# mcb-enhancer-v5.net
KiCad netlist of a schematic drawn in EAGLE
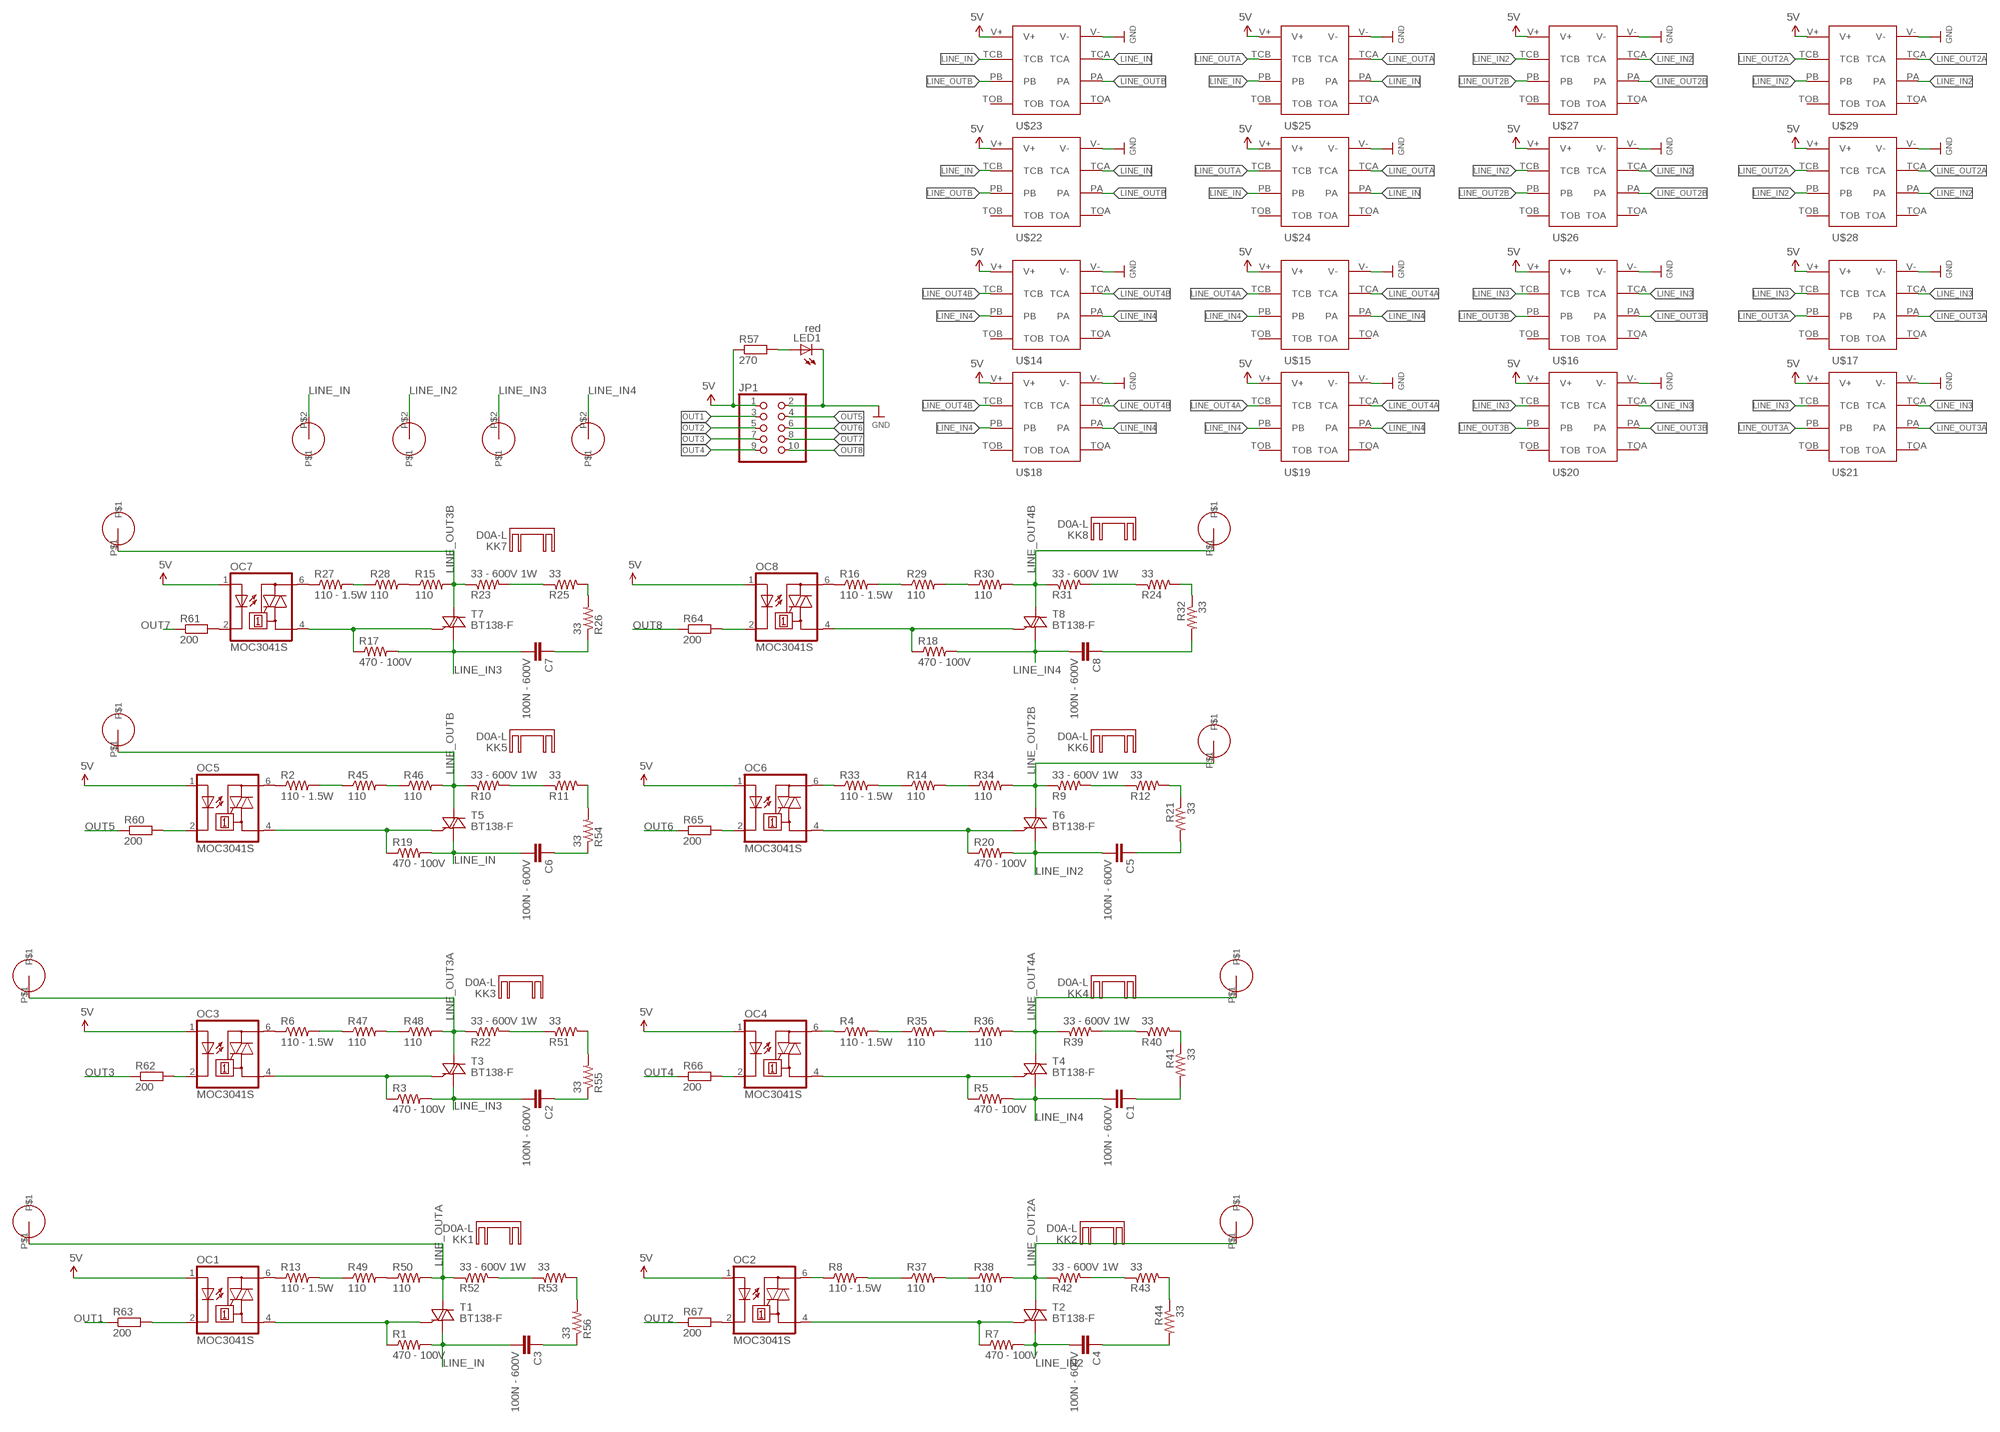
[diagram p0: schematic, sheet 1]

(export (version "E")
  (design (tool "Eeschema 10.0.6"))
  (components
    (comp (ref "C1")
      (value "100N - 600V")
      (footprint "eagle-import:C1210")
      (libsource (lib "eagle-import") (part "C-EUC1210"))
    )
    (comp (ref "C2")
      (value "100N - 600V")
      (footprint "eagle-import:C1210")
      (libsource (lib "eagle-import") (part "C-EUC1210"))
    )
    (comp (ref "C3")
      (value "100N - 600V")
      (footprint "eagle-import:C1210")
      (libsource (lib "eagle-import") (part "C-EUC1210"))
    )
    (comp (ref "C4")
      (value "100N - 600V")
      (footprint "eagle-import:C1210")
      (libsource (lib "eagle-import") (part "C-EUC1210"))
    )
    (comp (ref "C5")
      (value "100N - 600V")
      (footprint "eagle-import:C1210")
      (libsource (lib "eagle-import") (part "C-EUC1210"))
    )
    (comp (ref "C6")
      (value "100N - 600V")
      (footprint "eagle-import:C1210")
      (libsource (lib "eagle-import") (part "C-EUC1210"))
    )
    (comp (ref "C7")
      (value "100N - 600V")
      (footprint "eagle-import:C1210")
      (libsource (lib "eagle-import") (part "C-EUC1210"))
    )
    (comp (ref "C8")
      (value "100N - 600V")
      (footprint "eagle-import:C1210")
      (libsource (lib "eagle-import") (part "C-EUC1210"))
    )
    (comp (ref "JP1")
      (value "PINHD-2X5")
      (footprint "eagle-import:2X05")
      (libsource (lib "eagle-import") (part "PINHD-2X5"))
    )
    (comp (ref "KK1")
      (value "D0A-L")
      (footprint "eagle-import:D02A-L")
      (libsource (lib "eagle-import") (part "D0A-L"))
    )
    (comp (ref "KK2")
      (value "D0A-L")
      (footprint "eagle-import:D02A-L")
      (libsource (lib "eagle-import") (part "D0A-L"))
    )
    (comp (ref "KK3")
      (value "D0A-L")
      (footprint "eagle-import:D02A-L")
      (libsource (lib "eagle-import") (part "D0A-L"))
    )
    (comp (ref "KK4")
      (value "D0A-L")
      (footprint "eagle-import:D02A-L")
      (libsource (lib "eagle-import") (part "D0A-L"))
    )
    (comp (ref "KK5")
      (value "D0A-L")
      (footprint "eagle-import:D02A-L")
      (libsource (lib "eagle-import") (part "D0A-L"))
    )
    (comp (ref "KK6")
      (value "D0A-L")
      (footprint "eagle-import:D02A-L")
      (libsource (lib "eagle-import") (part "D0A-L"))
    )
    (comp (ref "KK7")
      (value "D0A-L")
      (footprint "eagle-import:D02A-L")
      (libsource (lib "eagle-import") (part "D0A-L"))
    )
    (comp (ref "KK8")
      (value "D0A-L")
      (footprint "eagle-import:D02A-L")
      (libsource (lib "eagle-import") (part "D0A-L"))
    )
    (comp (ref "LED1")
      (value "red")
      (footprint "eagle-import:CHIP-LED0805")
      (libsource (lib "eagle-import") (part "LEDCHIP-LED0805"))
    )
    (comp (ref "OC1")
      (value "MOC3041S")
      (footprint "eagle-import:DIL6-SMD")
      (fields
        (field (name "MF") "FAIRCHILD SEMICONDUCTOR")
        (field (name "MPN") "MOC3041S-M")
        (field (name "MPN_1") "MOC3033S-M")
        (field (name "OC_FARNELL") "unknown")
        (field (name "OC_NEWARK") "05C2878")
      )
      (libsource (lib "eagle-import") (part "MOC30S41"))
    )
    (comp (ref "OC2")
      (value "MOC3041S")
      (footprint "eagle-import:DIL6-SMD")
      (fields
        (field (name "MF") "FAIRCHILD SEMICONDUCTOR")
        (field (name "MPN") "MOC3041S-M")
        (field (name "MPN_1") "MOC3033S-M")
        (field (name "OC_FARNELL") "unknown")
        (field (name "OC_NEWARK") "05C2878")
      )
      (libsource (lib "eagle-import") (part "MOC30S41"))
    )
    (comp (ref "OC3")
      (value "MOC3041S")
      (footprint "eagle-import:DIL6-SMD")
      (fields
        (field (name "MF") "FAIRCHILD SEMICONDUCTOR")
        (field (name "MPN") "MOC3041S-M")
        (field (name "MPN_1") "MOC3033S-M")
        (field (name "OC_FARNELL") "unknown")
        (field (name "OC_NEWARK") "05C2878")
      )
      (libsource (lib "eagle-import") (part "MOC30S41"))
    )
    (comp (ref "OC4")
      (value "MOC3041S")
      (footprint "eagle-import:DIL6-SMD")
      (fields
        (field (name "MF") "FAIRCHILD SEMICONDUCTOR")
        (field (name "MPN") "MOC3041S-M")
        (field (name "MPN_1") "MOC3033S-M")
        (field (name "OC_FARNELL") "unknown")
        (field (name "OC_NEWARK") "05C2878")
      )
      (libsource (lib "eagle-import") (part "MOC30S41"))
    )
    (comp (ref "OC5")
      (value "MOC3041S")
      (footprint "eagle-import:DIL6-SMD")
      (fields
        (field (name "MF") "FAIRCHILD SEMICONDUCTOR")
        (field (name "MPN") "MOC3041S-M")
        (field (name "MPN_1") "MOC3033S-M")
        (field (name "OC_FARNELL") "unknown")
        (field (name "OC_NEWARK") "05C2878")
      )
      (libsource (lib "eagle-import") (part "MOC30S41"))
    )
    (comp (ref "OC6")
      (value "MOC3041S")
      (footprint "eagle-import:DIL6-SMD")
      (fields
        (field (name "MF") "FAIRCHILD SEMICONDUCTOR")
        (field (name "MPN") "MOC3041S-M")
        (field (name "MPN_1") "MOC3033S-M")
        (field (name "OC_FARNELL") "unknown")
        (field (name "OC_NEWARK") "05C2878")
      )
      (libsource (lib "eagle-import") (part "MOC30S41"))
    )
    (comp (ref "OC7")
      (value "MOC3041S")
      (footprint "eagle-import:DIL6-SMD")
      (fields
        (field (name "MF") "FAIRCHILD SEMICONDUCTOR")
        (field (name "MPN") "MOC3041S-M")
        (field (name "MPN_1") "MOC3033S-M")
        (field (name "OC_FARNELL") "unknown")
        (field (name "OC_NEWARK") "05C2878")
      )
      (libsource (lib "eagle-import") (part "MOC30S41"))
    )
    (comp (ref "OC8")
      (value "MOC3041S")
      (footprint "eagle-import:DIL6-SMD")
      (fields
        (field (name "MF") "FAIRCHILD SEMICONDUCTOR")
        (field (name "MPN") "MOC3041S-M")
        (field (name "MPN_1") "MOC3033S-M")
        (field (name "OC_FARNELL") "unknown")
        (field (name "OC_NEWARK") "05C2878")
      )
      (libsource (lib "eagle-import") (part "MOC30S41"))
    )
    (comp (ref "R1")
      (value "470 - 100V")
      (footprint "eagle-import:R1206")
      (libsource (lib "eagle-import") (part "R-US_R1206"))
    )
    (comp (ref "R2")
      (value "110 - 1.5W")
      (footprint "eagle-import:R2512")
      (libsource (lib "eagle-import") (part "R-US_R2512"))
    )
    (comp (ref "R3")
      (value "470 - 100V")
      (footprint "eagle-import:R1206")
      (libsource (lib "eagle-import") (part "R-US_R1206"))
    )
    (comp (ref "R4")
      (value "110 - 1.5W")
      (footprint "eagle-import:R2512")
      (libsource (lib "eagle-import") (part "R-US_R2512"))
    )
    (comp (ref "R5")
      (value "470 - 100V")
      (footprint "eagle-import:R1206")
      (libsource (lib "eagle-import") (part "R-US_R1206"))
    )
    (comp (ref "R6")
      (value "110 - 1.5W")
      (footprint "eagle-import:R2512")
      (libsource (lib "eagle-import") (part "R-US_R2512"))
    )
    (comp (ref "R7")
      (value "470 - 100V")
      (footprint "eagle-import:R1206")
      (libsource (lib "eagle-import") (part "R-US_R1206"))
    )
    (comp (ref "R8")
      (value "110 - 1.5W")
      (footprint "eagle-import:R2512")
      (libsource (lib "eagle-import") (part "R-US_R2512"))
    )
    (comp (ref "R9")
      (value "33 - 600V 1W")
      (footprint "eagle-import:R1206")
      (libsource (lib "eagle-import") (part "R-US_R1206"))
    )
    (comp (ref "R10")
      (value "33 - 600V 1W")
      (footprint "eagle-import:R1206")
      (libsource (lib "eagle-import") (part "R-US_R1206"))
    )
    (comp (ref "R11")
      (value "33")
      (footprint "eagle-import:R1206")
      (libsource (lib "eagle-import") (part "R-US_R1206"))
    )
    (comp (ref "R12")
      (value "33")
      (footprint "eagle-import:R1206")
      (libsource (lib "eagle-import") (part "R-US_R1206"))
    )
    (comp (ref "R13")
      (value "110 - 1.5W")
      (footprint "eagle-import:R2512")
      (libsource (lib "eagle-import") (part "R-US_R2512"))
    )
    (comp (ref "R14")
      (value "110")
      (footprint "eagle-import:R2512")
      (libsource (lib "eagle-import") (part "R-US_R2512"))
    )
    (comp (ref "R15")
      (value "110")
      (footprint "eagle-import:R2512")
      (libsource (lib "eagle-import") (part "R-US_R2512"))
    )
    (comp (ref "R16")
      (value "110 - 1.5W")
      (footprint "eagle-import:R2512")
      (libsource (lib "eagle-import") (part "R-US_R2512"))
    )
    (comp (ref "R17")
      (value "470 - 100V")
      (footprint "eagle-import:R1206")
      (libsource (lib "eagle-import") (part "R-US_R1206"))
    )
    (comp (ref "R18")
      (value "470 - 100V")
      (footprint "eagle-import:R1206")
      (libsource (lib "eagle-import") (part "R-US_R1206"))
    )
    (comp (ref "R19")
      (value "470 - 100V")
      (footprint "eagle-import:R1206")
      (libsource (lib "eagle-import") (part "R-US_R1206"))
    )
    (comp (ref "R20")
      (value "470 - 100V")
      (footprint "eagle-import:R1206")
      (libsource (lib "eagle-import") (part "R-US_R1206"))
    )
    (comp (ref "R21")
      (value "33")
      (footprint "eagle-import:R1206")
      (libsource (lib "eagle-import") (part "R-US_R1206"))
    )
    (comp (ref "R22")
      (value "33 - 600V 1W")
      (footprint "eagle-import:R1206")
      (libsource (lib "eagle-import") (part "R-US_R1206"))
    )
    (comp (ref "R23")
      (value "33 - 600V 1W")
      (footprint "eagle-import:R1206")
      (libsource (lib "eagle-import") (part "R-US_R1206"))
    )
    (comp (ref "R24")
      (value "33")
      (footprint "eagle-import:R1206")
      (libsource (lib "eagle-import") (part "R-US_R1206"))
    )
    (comp (ref "R25")
      (value "33")
      (footprint "eagle-import:R1206")
      (libsource (lib "eagle-import") (part "R-US_R1206"))
    )
    (comp (ref "R26")
      (value "33")
      (footprint "eagle-import:R1206")
      (libsource (lib "eagle-import") (part "R-US_R1206"))
    )
    (comp (ref "R27")
      (value "110 - 1.5W")
      (footprint "eagle-import:R2512")
      (libsource (lib "eagle-import") (part "R-US_R2512"))
    )
    (comp (ref "R28")
      (value "110")
      (footprint "eagle-import:R2512")
      (libsource (lib "eagle-import") (part "R-US_R2512"))
    )
    (comp (ref "R29")
      (value "110")
      (footprint "eagle-import:R2512")
      (libsource (lib "eagle-import") (part "R-US_R2512"))
    )
    (comp (ref "R30")
      (value "110")
      (footprint "eagle-import:R2512")
      (libsource (lib "eagle-import") (part "R-US_R2512"))
    )
    (comp (ref "R31")
      (value "33 - 600V 1W")
      (footprint "eagle-import:R1206")
      (libsource (lib "eagle-import") (part "R-US_R1206"))
    )
    (comp (ref "R32")
      (value "33")
      (footprint "eagle-import:R1206")
      (libsource (lib "eagle-import") (part "R-US_R1206"))
    )
    (comp (ref "R33")
      (value "110 - 1.5W")
      (footprint "eagle-import:R2512")
      (libsource (lib "eagle-import") (part "R-US_R2512"))
    )
    (comp (ref "R34")
      (value "110")
      (footprint "eagle-import:R2512")
      (libsource (lib "eagle-import") (part "R-US_R2512"))
    )
    (comp (ref "R35")
      (value "110")
      (footprint "eagle-import:R2512")
      (libsource (lib "eagle-import") (part "R-US_R2512"))
    )
    (comp (ref "R36")
      (value "110")
      (footprint "eagle-import:R2512")
      (libsource (lib "eagle-import") (part "R-US_R2512"))
    )
    (comp (ref "R37")
      (value "110")
      (footprint "eagle-import:R2512")
      (libsource (lib "eagle-import") (part "R-US_R2512"))
    )
    (comp (ref "R38")
      (value "110")
      (footprint "eagle-import:R2512")
      (libsource (lib "eagle-import") (part "R-US_R2512"))
    )
    (comp (ref "R39")
      (value "33 - 600V 1W")
      (footprint "eagle-import:R1206")
      (libsource (lib "eagle-import") (part "R-US_R1206"))
    )
    (comp (ref "R40")
      (value "33")
      (footprint "eagle-import:R1206")
      (libsource (lib "eagle-import") (part "R-US_R1206"))
    )
    (comp (ref "R41")
      (value "33")
      (footprint "eagle-import:R1206")
      (libsource (lib "eagle-import") (part "R-US_R1206"))
    )
    (comp (ref "R42")
      (value "33 - 600V 1W")
      (footprint "eagle-import:R1206")
      (libsource (lib "eagle-import") (part "R-US_R1206"))
    )
    (comp (ref "R43")
      (value "33")
      (footprint "eagle-import:R1206")
      (libsource (lib "eagle-import") (part "R-US_R1206"))
    )
    (comp (ref "R44")
      (value "33")
      (footprint "eagle-import:R1206")
      (libsource (lib "eagle-import") (part "R-US_R1206"))
    )
    (comp (ref "R45")
      (value "110")
      (footprint "eagle-import:R2512")
      (libsource (lib "eagle-import") (part "R-US_R2512"))
    )
    (comp (ref "R46")
      (value "110")
      (footprint "eagle-import:R2512")
      (libsource (lib "eagle-import") (part "R-US_R2512"))
    )
    (comp (ref "R47")
      (value "110")
      (footprint "eagle-import:R2512")
      (libsource (lib "eagle-import") (part "R-US_R2512"))
    )
    (comp (ref "R48")
      (value "110")
      (footprint "eagle-import:R2512")
      (libsource (lib "eagle-import") (part "R-US_R2512"))
    )
    (comp (ref "R49")
      (value "110")
      (footprint "eagle-import:R2512")
      (libsource (lib "eagle-import") (part "R-US_R2512"))
    )
    (comp (ref "R50")
      (value "110")
      (footprint "eagle-import:R2512")
      (libsource (lib "eagle-import") (part "R-US_R2512"))
    )
    (comp (ref "R51")
      (value "33")
      (footprint "eagle-import:R1206")
      (libsource (lib "eagle-import") (part "R-US_R1206"))
    )
    (comp (ref "R52")
      (value "33 - 600V 1W")
      (footprint "eagle-import:R1206")
      (libsource (lib "eagle-import") (part "R-US_R1206"))
    )
    (comp (ref "R53")
      (value "33")
      (footprint "eagle-import:R1206")
      (libsource (lib "eagle-import") (part "R-US_R1206"))
    )
    (comp (ref "R54")
      (value "33")
      (footprint "eagle-import:R1206")
      (libsource (lib "eagle-import") (part "R-US_R1206"))
    )
    (comp (ref "R55")
      (value "33")
      (footprint "eagle-import:R1206")
      (libsource (lib "eagle-import") (part "R-US_R1206"))
    )
    (comp (ref "R56")
      (value "33")
      (footprint "eagle-import:R1206")
      (libsource (lib "eagle-import") (part "R-US_R1206"))
    )
    (comp (ref "R57")
      (value "270")
      (footprint "eagle-import:R0402")
      (libsource (lib "eagle-import") (part "resistor_R-EU_R0402"))
    )
    (comp (ref "R60")
      (value "200")
      (footprint "eagle-import:R0603")
      (libsource (lib "eagle-import") (part "R-EU_R0603"))
    )
    (comp (ref "R61")
      (value "200")
      (footprint "eagle-import:R0603")
      (libsource (lib "eagle-import") (part "R-EU_R0603"))
    )
    (comp (ref "R62")
      (value "200")
      (footprint "eagle-import:R0603")
      (libsource (lib "eagle-import") (part "R-EU_R0603"))
    )
    (comp (ref "R63")
      (value "200")
      (footprint "eagle-import:R0603")
      (libsource (lib "eagle-import") (part "R-EU_R0603"))
    )
    (comp (ref "R64")
      (value "200")
      (footprint "eagle-import:R0603")
      (libsource (lib "eagle-import") (part "R-EU_R0603"))
    )
    (comp (ref "R65")
      (value "200")
      (footprint "eagle-import:R0603")
      (libsource (lib "eagle-import") (part "R-EU_R0603"))
    )
    (comp (ref "R66")
      (value "200")
      (footprint "eagle-import:R0603")
      (libsource (lib "eagle-import") (part "R-EU_R0603"))
    )
    (comp (ref "R67")
      (value "200")
      (footprint "eagle-import:R0603")
      (libsource (lib "eagle-import") (part "R-EU_R0603"))
    )
    (comp (ref "T1")
      (value "BT138-F")
      (footprint "eagle-import:TO220BF")
      (libsource (lib "eagle-import") (part "BT138-F"))
    )
    (comp (ref "T2")
      (value "BT138-F")
      (footprint "eagle-import:TO220BF")
      (libsource (lib "eagle-import") (part "BT138-F"))
    )
    (comp (ref "T3")
      (value "BT138-F")
      (footprint "eagle-import:TO220BF")
      (libsource (lib "eagle-import") (part "BT138-F"))
    )
    (comp (ref "T4")
      (value "BT138-F")
      (footprint "eagle-import:TO220BF")
      (libsource (lib "eagle-import") (part "BT138-F"))
    )
    (comp (ref "T5")
      (value "BT138-F")
      (footprint "eagle-import:TO220BF")
      (libsource (lib "eagle-import") (part "BT138-F"))
    )
    (comp (ref "T6")
      (value "BT138-F")
      (footprint "eagle-import:TO220BF")
      (libsource (lib "eagle-import") (part "BT138-F"))
    )
    (comp (ref "T7")
      (value "BT138-F")
      (footprint "eagle-import:TO220BF")
      (libsource (lib "eagle-import") (part "BT138-F"))
    )
    (comp (ref "T8")
      (value "BT138-F")
      (footprint "eagle-import:TO220BF")
      (libsource (lib "eagle-import") (part "BT138-F"))
    )
    (comp (ref "U$1")
      (value "CONN-SCREW-MINI")
      (footprint "eagle-import:CONN-SCREW-MINI")
      (libsource (lib "eagle-import") (part "CONN-SCREW-MINI"))
    )
    (comp (ref "U$2")
      (value "CONN-SCREW-MINI")
      (footprint "eagle-import:CONN-SCREW-MINI")
      (libsource (lib "eagle-import") (part "CONN-SCREW-MINI"))
    )
    (comp (ref "U$3")
      (value "CONN-SCREW-MINI")
      (footprint "eagle-import:CONN-SCREW-MINI")
      (libsource (lib "eagle-import") (part "CONN-SCREW-MINI"))
    )
    (comp (ref "U$4")
      (value "CONN-SCREW-MINI")
      (footprint "eagle-import:CONN-SCREW-MINI")
      (libsource (lib "eagle-import") (part "CONN-SCREW-MINI"))
    )
    (comp (ref "U$5")
      (value "CONN-SCREW-MINI")
      (footprint "eagle-import:CONN-SCREW-MINI")
      (libsource (lib "eagle-import") (part "CONN-SCREW-MINI"))
    )
    (comp (ref "U$6")
      (value "CONN-SCREW-MINI")
      (footprint "eagle-import:CONN-SCREW-MINI")
      (libsource (lib "eagle-import") (part "CONN-SCREW-MINI"))
    )
    (comp (ref "U$7")
      (value "CONN-SCREW-MINI")
      (footprint "eagle-import:CONN-SCREW-MINI")
      (libsource (lib "eagle-import") (part "CONN-SCREW-MINI"))
    )
    (comp (ref "U$8")
      (value "CONN-SCREW-MINI")
      (footprint "eagle-import:CONN-SCREW-MINI")
      (libsource (lib "eagle-import") (part "CONN-SCREW-MINI"))
    )
    (comp (ref "U$9")
      (value "CONN")
      (footprint "eagle-import:HC617")
      (libsource (lib "eagle-import") (part "CONN"))
    )
    (comp (ref "U$10")
      (value "CONN")
      (footprint "eagle-import:HC617")
      (libsource (lib "eagle-import") (part "CONN"))
    )
    (comp (ref "U$11")
      (value "CONN")
      (footprint "eagle-import:HC617")
      (libsource (lib "eagle-import") (part "CONN"))
    )
    (comp (ref "U$12")
      (value "CONN")
      (footprint "eagle-import:HC617")
      (libsource (lib "eagle-import") (part "CONN"))
    )
    (comp (ref "U$14")
      (value "9-1462038-9")
      (footprint "eagle-import:TE-9-1462038-9")
      (libsource (lib "eagle-import") (part "9-1462038-9"))
    )
    (comp (ref "U$15")
      (value "9-1462038-9")
      (footprint "eagle-import:TE-9-1462038-9")
      (libsource (lib "eagle-import") (part "9-1462038-9"))
    )
    (comp (ref "U$16")
      (value "9-1462038-9")
      (footprint "eagle-import:TE-9-1462038-9")
      (libsource (lib "eagle-import") (part "9-1462038-9"))
    )
    (comp (ref "U$17")
      (value "9-1462038-9")
      (footprint "eagle-import:TE-9-1462038-9")
      (libsource (lib "eagle-import") (part "9-1462038-9"))
    )
    (comp (ref "U$18")
      (value "9-1462038-9")
      (footprint "eagle-import:TE-9-1462038-9")
      (libsource (lib "eagle-import") (part "9-1462038-9"))
    )
    (comp (ref "U$19")
      (value "9-1462038-9")
      (footprint "eagle-import:TE-9-1462038-9")
      (libsource (lib "eagle-import") (part "9-1462038-9"))
    )
    (comp (ref "U$20")
      (value "9-1462038-9")
      (footprint "eagle-import:TE-9-1462038-9")
      (libsource (lib "eagle-import") (part "9-1462038-9"))
    )
    (comp (ref "U$21")
      (value "9-1462038-9")
      (footprint "eagle-import:TE-9-1462038-9")
      (libsource (lib "eagle-import") (part "9-1462038-9"))
    )
    (comp (ref "U$22")
      (value "9-1462038-9")
      (footprint "eagle-import:TE-9-1462038-9")
      (libsource (lib "eagle-import") (part "9-1462038-9"))
    )
    (comp (ref "U$23")
      (value "9-1462038-9")
      (footprint "eagle-import:TE-9-1462038-9")
      (libsource (lib "eagle-import") (part "9-1462038-9"))
    )
    (comp (ref "U$24")
      (value "9-1462038-9")
      (footprint "eagle-import:TE-9-1462038-9")
      (libsource (lib "eagle-import") (part "9-1462038-9"))
    )
    (comp (ref "U$25")
      (value "9-1462038-9")
      (footprint "eagle-import:TE-9-1462038-9")
      (libsource (lib "eagle-import") (part "9-1462038-9"))
    )
    (comp (ref "U$26")
      (value "9-1462038-9")
      (footprint "eagle-import:TE-9-1462038-9")
      (libsource (lib "eagle-import") (part "9-1462038-9"))
    )
    (comp (ref "U$27")
      (value "9-1462038-9")
      (footprint "eagle-import:TE-9-1462038-9")
      (libsource (lib "eagle-import") (part "9-1462038-9"))
    )
    (comp (ref "U$28")
      (value "9-1462038-9")
      (footprint "eagle-import:TE-9-1462038-9")
      (libsource (lib "eagle-import") (part "9-1462038-9"))
    )
    (comp (ref "U$29")
      (value "9-1462038-9")
      (footprint "eagle-import:TE-9-1462038-9")
      (libsource (lib "eagle-import") (part "9-1462038-9"))
    )
  )
  (nets
    (net (code "1") (name "5V") (class "Default")
      (node (ref "JP1") (pin "1") (pinfunction "1_1") (pintype "passive"))
      (node (ref "OC1") (pin "1") (pinfunction "A_1") (pintype "passive"))
      (node (ref "OC2") (pin "1") (pinfunction "A_1") (pintype "passive"))
      (node (ref "OC3") (pin "1") (pinfunction "A_1") (pintype "passive"))
      (node (ref "OC4") (pin "1") (pinfunction "A_1") (pintype "passive"))
      (node (ref "OC5") (pin "1") (pinfunction "A_1") (pintype "passive"))
      (node (ref "OC6") (pin "1") (pinfunction "A_1") (pintype "passive"))
      (node (ref "OC7") (pin "1") (pinfunction "A_1") (pintype "passive"))
      (node (ref "OC8") (pin "1") (pinfunction "A_1") (pintype "passive"))
      (node (ref "R57") (pin "1") (pinfunction "1_1") (pintype "passive"))
      (node (ref "U$14") (pin "V+") (pinfunction "V+_V+") (pintype "bidirectional"))
      (node (ref "U$15") (pin "V+") (pinfunction "V+_V+") (pintype "bidirectional"))
      (node (ref "U$16") (pin "V+") (pinfunction "V+_V+") (pintype "bidirectional"))
      (node (ref "U$17") (pin "V+") (pinfunction "V+_V+") (pintype "bidirectional"))
      (node (ref "U$18") (pin "V+") (pinfunction "V+_V+") (pintype "bidirectional"))
      (node (ref "U$19") (pin "V+") (pinfunction "V+_V+") (pintype "bidirectional"))
      (node (ref "U$20") (pin "V+") (pinfunction "V+_V+") (pintype "bidirectional"))
      (node (ref "U$21") (pin "V+") (pinfunction "V+_V+") (pintype "bidirectional"))
      (node (ref "U$22") (pin "V+") (pinfunction "V+_V+") (pintype "bidirectional"))
      (node (ref "U$23") (pin "V+") (pinfunction "V+_V+") (pintype "bidirectional"))
      (node (ref "U$24") (pin "V+") (pinfunction "V+_V+") (pintype "bidirectional"))
      (node (ref "U$25") (pin "V+") (pinfunction "V+_V+") (pintype "bidirectional"))
      (node (ref "U$26") (pin "V+") (pinfunction "V+_V+") (pintype "bidirectional"))
      (node (ref "U$27") (pin "V+") (pinfunction "V+_V+") (pintype "bidirectional"))
      (node (ref "U$28") (pin "V+") (pinfunction "V+_V+") (pintype "bidirectional"))
      (node (ref "U$29") (pin "V+") (pinfunction "V+_V+") (pintype "bidirectional"))
    )
    (net (code "2") (name "GND") (class "Default")
      (node (ref "JP1") (pin "2") (pinfunction "2_2") (pintype "passive"))
      (node (ref "LED1") (pin "C") (pinfunction "C_C") (pintype "passive"))
      (node (ref "U$14") (pin "V-") (pinfunction "V-_V-") (pintype "bidirectional"))
      (node (ref "U$15") (pin "V-") (pinfunction "V-_V-") (pintype "bidirectional"))
      (node (ref "U$16") (pin "V-") (pinfunction "V-_V-") (pintype "bidirectional"))
      (node (ref "U$17") (pin "V-") (pinfunction "V-_V-") (pintype "bidirectional"))
      (node (ref "U$18") (pin "V-") (pinfunction "V-_V-") (pintype "bidirectional"))
      (node (ref "U$19") (pin "V-") (pinfunction "V-_V-") (pintype "bidirectional"))
      (node (ref "U$20") (pin "V-") (pinfunction "V-_V-") (pintype "bidirectional"))
      (node (ref "U$21") (pin "V-") (pinfunction "V-_V-") (pintype "bidirectional"))
      (node (ref "U$22") (pin "V-") (pinfunction "V-_V-") (pintype "bidirectional"))
      (node (ref "U$23") (pin "V-") (pinfunction "V-_V-") (pintype "bidirectional"))
      (node (ref "U$24") (pin "V-") (pinfunction "V-_V-") (pintype "bidirectional"))
      (node (ref "U$25") (pin "V-") (pinfunction "V-_V-") (pintype "bidirectional"))
      (node (ref "U$26") (pin "V-") (pinfunction "V-_V-") (pintype "bidirectional"))
      (node (ref "U$27") (pin "V-") (pinfunction "V-_V-") (pintype "bidirectional"))
      (node (ref "U$28") (pin "V-") (pinfunction "V-_V-") (pintype "bidirectional"))
      (node (ref "U$29") (pin "V-") (pinfunction "V-_V-") (pintype "bidirectional"))
    )
    (net (code "3") (name "LINE_IN") (class "Default")
      (node (ref "C3") (pin "2") (pinfunction "2_2") (pintype "passive"))
      (node (ref "C6") (pin "2") (pinfunction "2_2") (pintype "passive"))
      (node (ref "R1") (pin "2") (pinfunction "2_2") (pintype "passive"))
      (node (ref "R19") (pin "2") (pinfunction "2_2") (pintype "passive"))
      (node (ref "T1") (pin "T1") (pinfunction "A1_T1") (pintype "passive"))
      (node (ref "T5") (pin "T1") (pinfunction "A1_T1") (pintype "passive"))
      (node (ref "U$22") (pin "TCA") (pinfunction "TCA_TCA") (pintype "bidirectional"))
      (node (ref "U$22") (pin "TCB") (pinfunction "TCB_TCB") (pintype "bidirectional"))
      (node (ref "U$23") (pin "TCA") (pinfunction "TCA_TCA") (pintype "bidirectional"))
      (node (ref "U$23") (pin "TCB") (pinfunction "TCB_TCB") (pintype "bidirectional"))
      (node (ref "U$24") (pin "PA") (pinfunction "PA_PA") (pintype "bidirectional"))
      (node (ref "U$24") (pin "PB") (pinfunction "PB_PB") (pintype "bidirectional"))
      (node (ref "U$25") (pin "PA") (pinfunction "PA_PA") (pintype "bidirectional"))
      (node (ref "U$25") (pin "PB") (pinfunction "PB_PB") (pintype "bidirectional"))
      (node (ref "U$9") (pin "P$2") (pinfunction "P$1_P$2") (pintype "bidirectional"))
    )
    (net (code "4") (name "LINE_IN2") (class "Default")
      (node (ref "C4") (pin "2") (pinfunction "2_2") (pintype "passive"))
      (node (ref "C5") (pin "2") (pinfunction "2_2") (pintype "passive"))
      (node (ref "R20") (pin "2") (pinfunction "2_2") (pintype "passive"))
      (node (ref "R7") (pin "2") (pinfunction "2_2") (pintype "passive"))
      (node (ref "T2") (pin "T1") (pinfunction "A1_T1") (pintype "passive"))
      (node (ref "T6") (pin "T1") (pinfunction "A1_T1") (pintype "passive"))
      (node (ref "U$10") (pin "P$2") (pinfunction "P$1_P$2") (pintype "bidirectional"))
      (node (ref "U$26") (pin "TCA") (pinfunction "TCA_TCA") (pintype "bidirectional"))
      (node (ref "U$26") (pin "TCB") (pinfunction "TCB_TCB") (pintype "bidirectional"))
      (node (ref "U$27") (pin "TCA") (pinfunction "TCA_TCA") (pintype "bidirectional"))
      (node (ref "U$27") (pin "TCB") (pinfunction "TCB_TCB") (pintype "bidirectional"))
      (node (ref "U$28") (pin "PA") (pinfunction "PA_PA") (pintype "bidirectional"))
      (node (ref "U$28") (pin "PB") (pinfunction "PB_PB") (pintype "bidirectional"))
      (node (ref "U$29") (pin "PA") (pinfunction "PA_PA") (pintype "bidirectional"))
      (node (ref "U$29") (pin "PB") (pinfunction "PB_PB") (pintype "bidirectional"))
    )
    (net (code "5") (name "LINE_IN3") (class "Default")
      (node (ref "C2") (pin "2") (pinfunction "2_2") (pintype "passive"))
      (node (ref "C7") (pin "2") (pinfunction "2_2") (pintype "passive"))
      (node (ref "R17") (pin "2") (pinfunction "2_2") (pintype "passive"))
      (node (ref "R3") (pin "2") (pinfunction "2_2") (pintype "passive"))
      (node (ref "T3") (pin "T1") (pinfunction "A1_T1") (pintype "passive"))
      (node (ref "T7") (pin "T1") (pinfunction "A1_T1") (pintype "passive"))
      (node (ref "U$11") (pin "P$2") (pinfunction "P$1_P$2") (pintype "bidirectional"))
      (node (ref "U$16") (pin "TCA") (pinfunction "TCA_TCA") (pintype "bidirectional"))
      (node (ref "U$16") (pin "TCB") (pinfunction "TCB_TCB") (pintype "bidirectional"))
      (node (ref "U$17") (pin "TCA") (pinfunction "TCA_TCA") (pintype "bidirectional"))
      (node (ref "U$17") (pin "TCB") (pinfunction "TCB_TCB") (pintype "bidirectional"))
      (node (ref "U$20") (pin "TCA") (pinfunction "TCA_TCA") (pintype "bidirectional"))
      (node (ref "U$20") (pin "TCB") (pinfunction "TCB_TCB") (pintype "bidirectional"))
      (node (ref "U$21") (pin "TCA") (pinfunction "TCA_TCA") (pintype "bidirectional"))
      (node (ref "U$21") (pin "TCB") (pinfunction "TCB_TCB") (pintype "bidirectional"))
    )
    (net (code "6") (name "LINE_IN4") (class "Default")
      (node (ref "C1") (pin "2") (pinfunction "2_2") (pintype "passive"))
      (node (ref "C8") (pin "2") (pinfunction "2_2") (pintype "passive"))
      (node (ref "R18") (pin "2") (pinfunction "2_2") (pintype "passive"))
      (node (ref "R5") (pin "2") (pinfunction "2_2") (pintype "passive"))
      (node (ref "T4") (pin "T1") (pinfunction "A1_T1") (pintype "passive"))
      (node (ref "T8") (pin "T1") (pinfunction "A1_T1") (pintype "passive"))
      (node (ref "U$12") (pin "P$2") (pinfunction "P$1_P$2") (pintype "bidirectional"))
      (node (ref "U$14") (pin "PA") (pinfunction "PA_PA") (pintype "bidirectional"))
      (node (ref "U$14") (pin "PB") (pinfunction "PB_PB") (pintype "bidirectional"))
      (node (ref "U$15") (pin "PA") (pinfunction "PA_PA") (pintype "bidirectional"))
      (node (ref "U$15") (pin "PB") (pinfunction "PB_PB") (pintype "bidirectional"))
      (node (ref "U$18") (pin "PA") (pinfunction "PA_PA") (pintype "bidirectional"))
      (node (ref "U$18") (pin "PB") (pinfunction "PB_PB") (pintype "bidirectional"))
      (node (ref "U$19") (pin "PA") (pinfunction "PA_PA") (pintype "bidirectional"))
      (node (ref "U$19") (pin "PB") (pinfunction "PB_PB") (pintype "bidirectional"))
    )
    (net (code "7") (name "LINE_OUT2A") (class "Default")
      (node (ref "R38") (pin "2") (pinfunction "2_2") (pintype "passive"))
      (node (ref "R42") (pin "1") (pinfunction "1_1") (pintype "passive"))
      (node (ref "T2") (pin "T2") (pinfunction "A2_T2") (pintype "passive"))
      (node (ref "U$2") (pin "P$1") (pinfunction "P$1_P$1") (pintype "bidirectional"))
      (node (ref "U$28") (pin "TCA") (pinfunction "TCA_TCA") (pintype "bidirectional"))
      (node (ref "U$28") (pin "TCB") (pinfunction "TCB_TCB") (pintype "bidirectional"))
      (node (ref "U$29") (pin "TCA") (pinfunction "TCA_TCA") (pintype "bidirectional"))
      (node (ref "U$29") (pin "TCB") (pinfunction "TCB_TCB") (pintype "bidirectional"))
    )
    (net (code "8") (name "LINE_OUT2B") (class "Default")
      (node (ref "R34") (pin "2") (pinfunction "2_2") (pintype "passive"))
      (node (ref "R9") (pin "1") (pinfunction "1_1") (pintype "passive"))
      (node (ref "T6") (pin "T2") (pinfunction "A2_T2") (pintype "passive"))
      (node (ref "U$26") (pin "PA") (pinfunction "PA_PA") (pintype "bidirectional"))
      (node (ref "U$26") (pin "PB") (pinfunction "PB_PB") (pintype "bidirectional"))
      (node (ref "U$27") (pin "PA") (pinfunction "PA_PA") (pintype "bidirectional"))
      (node (ref "U$27") (pin "PB") (pinfunction "PB_PB") (pintype "bidirectional"))
      (node (ref "U$6") (pin "P$1") (pinfunction "P$1_P$1") (pintype "bidirectional"))
    )
    (net (code "9") (name "LINE_OUT3A") (class "Default")
      (node (ref "R22") (pin "1") (pinfunction "1_1") (pintype "passive"))
      (node (ref "R48") (pin "2") (pinfunction "2_2") (pintype "passive"))
      (node (ref "T3") (pin "T2") (pinfunction "A2_T2") (pintype "passive"))
      (node (ref "U$17") (pin "PA") (pinfunction "PA_PA") (pintype "bidirectional"))
      (node (ref "U$17") (pin "PB") (pinfunction "PB_PB") (pintype "bidirectional"))
      (node (ref "U$21") (pin "PA") (pinfunction "PA_PA") (pintype "bidirectional"))
      (node (ref "U$21") (pin "PB") (pinfunction "PB_PB") (pintype "bidirectional"))
      (node (ref "U$3") (pin "P$1") (pinfunction "P$1_P$1") (pintype "bidirectional"))
    )
    (net (code "10") (name "LINE_OUT3B") (class "Default")
      (node (ref "R15") (pin "2") (pinfunction "2_2") (pintype "passive"))
      (node (ref "R23") (pin "1") (pinfunction "1_1") (pintype "passive"))
      (node (ref "T7") (pin "T2") (pinfunction "A2_T2") (pintype "passive"))
      (node (ref "U$16") (pin "PA") (pinfunction "PA_PA") (pintype "bidirectional"))
      (node (ref "U$16") (pin "PB") (pinfunction "PB_PB") (pintype "bidirectional"))
      (node (ref "U$20") (pin "PA") (pinfunction "PA_PA") (pintype "bidirectional"))
      (node (ref "U$20") (pin "PB") (pinfunction "PB_PB") (pintype "bidirectional"))
      (node (ref "U$7") (pin "P$1") (pinfunction "P$1_P$1") (pintype "bidirectional"))
    )
    (net (code "11") (name "LINE_OUT4A") (class "Default")
      (node (ref "R36") (pin "2") (pinfunction "2_2") (pintype "passive"))
      (node (ref "R39") (pin "1") (pinfunction "1_1") (pintype "passive"))
      (node (ref "T4") (pin "T2") (pinfunction "A2_T2") (pintype "passive"))
      (node (ref "U$15") (pin "TCA") (pinfunction "TCA_TCA") (pintype "bidirectional"))
      (node (ref "U$15") (pin "TCB") (pinfunction "TCB_TCB") (pintype "bidirectional"))
      (node (ref "U$19") (pin "TCA") (pinfunction "TCA_TCA") (pintype "bidirectional"))
      (node (ref "U$19") (pin "TCB") (pinfunction "TCB_TCB") (pintype "bidirectional"))
      (node (ref "U$4") (pin "P$1") (pinfunction "P$1_P$1") (pintype "bidirectional"))
    )
    (net (code "12") (name "LINE_OUT4B") (class "Default")
      (node (ref "R30") (pin "2") (pinfunction "2_2") (pintype "passive"))
      (node (ref "R31") (pin "1") (pinfunction "1_1") (pintype "passive"))
      (node (ref "T8") (pin "T2") (pinfunction "A2_T2") (pintype "passive"))
      (node (ref "U$14") (pin "TCA") (pinfunction "TCA_TCA") (pintype "bidirectional"))
      (node (ref "U$14") (pin "TCB") (pinfunction "TCB_TCB") (pintype "bidirectional"))
      (node (ref "U$18") (pin "TCA") (pinfunction "TCA_TCA") (pintype "bidirectional"))
      (node (ref "U$18") (pin "TCB") (pinfunction "TCB_TCB") (pintype "bidirectional"))
      (node (ref "U$8") (pin "P$1") (pinfunction "P$1_P$1") (pintype "bidirectional"))
    )
    (net (code "13") (name "LINE_OUTA") (class "Default")
      (node (ref "R50") (pin "2") (pinfunction "2_2") (pintype "passive"))
      (node (ref "R52") (pin "1") (pinfunction "1_1") (pintype "passive"))
      (node (ref "T1") (pin "T2") (pinfunction "A2_T2") (pintype "passive"))
      (node (ref "U$1") (pin "P$1") (pinfunction "P$1_P$1") (pintype "bidirectional"))
      (node (ref "U$24") (pin "TCA") (pinfunction "TCA_TCA") (pintype "bidirectional"))
      (node (ref "U$24") (pin "TCB") (pinfunction "TCB_TCB") (pintype "bidirectional"))
      (node (ref "U$25") (pin "TCA") (pinfunction "TCA_TCA") (pintype "bidirectional"))
      (node (ref "U$25") (pin "TCB") (pinfunction "TCB_TCB") (pintype "bidirectional"))
    )
    (net (code "14") (name "LINE_OUTB") (class "Default")
      (node (ref "R10") (pin "1") (pinfunction "1_1") (pintype "passive"))
      (node (ref "R46") (pin "2") (pinfunction "2_2") (pintype "passive"))
      (node (ref "T5") (pin "T2") (pinfunction "A2_T2") (pintype "passive"))
      (node (ref "U$22") (pin "PA") (pinfunction "PA_PA") (pintype "bidirectional"))
      (node (ref "U$22") (pin "PB") (pinfunction "PB_PB") (pintype "bidirectional"))
      (node (ref "U$23") (pin "PA") (pinfunction "PA_PA") (pintype "bidirectional"))
      (node (ref "U$23") (pin "PB") (pinfunction "PB_PB") (pintype "bidirectional"))
      (node (ref "U$5") (pin "P$1") (pinfunction "P$1_P$1") (pintype "bidirectional"))
    )
    (net (code "15") (name "Net-(C1-Pad1)") (class "Default")
      (node (ref "C1") (pin "1") (pinfunction "1_1") (pintype "passive"))
      (node (ref "R41") (pin "2") (pinfunction "2_2") (pintype "passive"))
    )
    (net (code "16") (name "Net-(C2-Pad1)") (class "Default")
      (node (ref "C2") (pin "1") (pinfunction "1_1") (pintype "passive"))
      (node (ref "R55") (pin "1") (pinfunction "1_1") (pintype "passive"))
    )
    (net (code "17") (name "Net-(C3-Pad1)") (class "Default")
      (node (ref "C3") (pin "1") (pinfunction "1_1") (pintype "passive"))
      (node (ref "R56") (pin "1") (pinfunction "1_1") (pintype "passive"))
    )
    (net (code "18") (name "Net-(C4-Pad1)") (class "Default")
      (node (ref "C4") (pin "1") (pinfunction "1_1") (pintype "passive"))
      (node (ref "R44") (pin "2") (pinfunction "2_2") (pintype "passive"))
    )
    (net (code "19") (name "Net-(C5-Pad1)") (class "Default")
      (node (ref "C5") (pin "1") (pinfunction "1_1") (pintype "passive"))
      (node (ref "R21") (pin "2") (pinfunction "2_2") (pintype "passive"))
    )
    (net (code "20") (name "Net-(C6-Pad1)") (class "Default")
      (node (ref "C6") (pin "1") (pinfunction "1_1") (pintype "passive"))
      (node (ref "R54") (pin "1") (pinfunction "1_1") (pintype "passive"))
    )
    (net (code "21") (name "Net-(C7-Pad1)") (class "Default")
      (node (ref "C7") (pin "1") (pinfunction "1_1") (pintype "passive"))
      (node (ref "R26") (pin "1") (pinfunction "1_1") (pintype "passive"))
    )
    (net (code "22") (name "Net-(C8-Pad1)") (class "Default")
      (node (ref "C8") (pin "1") (pinfunction "1_1") (pintype "passive"))
      (node (ref "R32") (pin "2") (pinfunction "2_2") (pintype "passive"))
    )
    (net (code "23") (name "Net-(LED1-PadA)") (class "Default")
      (node (ref "LED1") (pin "A") (pinfunction "A_A") (pintype "passive"))
      (node (ref "R57") (pin "2") (pinfunction "2_2") (pintype "passive"))
    )
    (net (code "24") (name "Net-(OC1-A1)") (class "Default")
      (node (ref "OC1") (pin "4") (pinfunction "A1_4") (pintype "passive"))
      (node (ref "R1") (pin "1") (pinfunction "1_1") (pintype "passive"))
      (node (ref "T1") (pin "G") (pinfunction "G_G") (pintype "passive"))
    )
    (net (code "25") (name "Net-(OC1-A2)") (class "Default")
      (node (ref "OC1") (pin "6") (pinfunction "A2_6") (pintype "passive"))
      (node (ref "R13") (pin "1") (pinfunction "1_1") (pintype "passive"))
    )
    (net (code "26") (name "Net-(OC1-C)") (class "Default")
      (node (ref "OC1") (pin "2") (pinfunction "C_2") (pintype "passive"))
      (node (ref "R63") (pin "2") (pinfunction "2_2") (pintype "passive"))
    )
    (net (code "27") (name "Net-(OC2-A1)") (class "Default")
      (node (ref "OC2") (pin "4") (pinfunction "A1_4") (pintype "passive"))
      (node (ref "R7") (pin "1") (pinfunction "1_1") (pintype "passive"))
      (node (ref "T2") (pin "G") (pinfunction "G_G") (pintype "passive"))
    )
    (net (code "28") (name "Net-(OC2-A2)") (class "Default")
      (node (ref "OC2") (pin "6") (pinfunction "A2_6") (pintype "passive"))
      (node (ref "R8") (pin "1") (pinfunction "1_1") (pintype "passive"))
    )
    (net (code "29") (name "Net-(OC2-C)") (class "Default")
      (node (ref "OC2") (pin "2") (pinfunction "C_2") (pintype "passive"))
      (node (ref "R67") (pin "2") (pinfunction "2_2") (pintype "passive"))
    )
    (net (code "30") (name "Net-(OC3-A1)") (class "Default")
      (node (ref "OC3") (pin "4") (pinfunction "A1_4") (pintype "passive"))
      (node (ref "R3") (pin "1") (pinfunction "1_1") (pintype "passive"))
      (node (ref "T3") (pin "G") (pinfunction "G_G") (pintype "passive"))
    )
    (net (code "31") (name "Net-(OC3-A2)") (class "Default")
      (node (ref "OC3") (pin "6") (pinfunction "A2_6") (pintype "passive"))
      (node (ref "R6") (pin "1") (pinfunction "1_1") (pintype "passive"))
    )
    (net (code "32") (name "Net-(OC3-C)") (class "Default")
      (node (ref "OC3") (pin "2") (pinfunction "C_2") (pintype "passive"))
      (node (ref "R62") (pin "2") (pinfunction "2_2") (pintype "passive"))
    )
    (net (code "33") (name "Net-(OC4-A1)") (class "Default")
      (node (ref "OC4") (pin "4") (pinfunction "A1_4") (pintype "passive"))
      (node (ref "R5") (pin "1") (pinfunction "1_1") (pintype "passive"))
      (node (ref "T4") (pin "G") (pinfunction "G_G") (pintype "passive"))
    )
    (net (code "34") (name "Net-(OC4-A2)") (class "Default")
      (node (ref "OC4") (pin "6") (pinfunction "A2_6") (pintype "passive"))
      (node (ref "R4") (pin "1") (pinfunction "1_1") (pintype "passive"))
    )
    (net (code "35") (name "Net-(OC4-C)") (class "Default")
      (node (ref "OC4") (pin "2") (pinfunction "C_2") (pintype "passive"))
      (node (ref "R66") (pin "2") (pinfunction "2_2") (pintype "passive"))
    )
    (net (code "36") (name "Net-(OC5-A1)") (class "Default")
      (node (ref "OC5") (pin "4") (pinfunction "A1_4") (pintype "passive"))
      (node (ref "R19") (pin "1") (pinfunction "1_1") (pintype "passive"))
      (node (ref "T5") (pin "G") (pinfunction "G_G") (pintype "passive"))
    )
    (net (code "37") (name "Net-(OC5-A2)") (class "Default")
      (node (ref "OC5") (pin "6") (pinfunction "A2_6") (pintype "passive"))
      (node (ref "R2") (pin "1") (pinfunction "1_1") (pintype "passive"))
    )
    (net (code "38") (name "Net-(OC5-C)") (class "Default")
      (node (ref "OC5") (pin "2") (pinfunction "C_2") (pintype "passive"))
      (node (ref "R60") (pin "2") (pinfunction "2_2") (pintype "passive"))
    )
    (net (code "39") (name "Net-(OC6-A1)") (class "Default")
      (node (ref "OC6") (pin "4") (pinfunction "A1_4") (pintype "passive"))
      (node (ref "R20") (pin "1") (pinfunction "1_1") (pintype "passive"))
      (node (ref "T6") (pin "G") (pinfunction "G_G") (pintype "passive"))
    )
    (net (code "40") (name "Net-(OC6-A2)") (class "Default")
      (node (ref "OC6") (pin "6") (pinfunction "A2_6") (pintype "passive"))
      (node (ref "R33") (pin "1") (pinfunction "1_1") (pintype "passive"))
    )
    (net (code "41") (name "Net-(OC6-C)") (class "Default")
      (node (ref "OC6") (pin "2") (pinfunction "C_2") (pintype "passive"))
      (node (ref "R65") (pin "2") (pinfunction "2_2") (pintype "passive"))
    )
    (net (code "42") (name "Net-(OC7-A1)") (class "Default")
      (node (ref "OC7") (pin "4") (pinfunction "A1_4") (pintype "passive"))
      (node (ref "R17") (pin "1") (pinfunction "1_1") (pintype "passive"))
      (node (ref "T7") (pin "G") (pinfunction "G_G") (pintype "passive"))
    )
    (net (code "43") (name "Net-(OC7-A2)") (class "Default")
      (node (ref "OC7") (pin "6") (pinfunction "A2_6") (pintype "passive"))
      (node (ref "R27") (pin "1") (pinfunction "1_1") (pintype "passive"))
    )
    (net (code "44") (name "Net-(OC7-C)") (class "Default")
      (node (ref "OC7") (pin "2") (pinfunction "C_2") (pintype "passive"))
      (node (ref "R61") (pin "2") (pinfunction "2_2") (pintype "passive"))
    )
    (net (code "45") (name "Net-(OC8-A1)") (class "Default")
      (node (ref "OC8") (pin "4") (pinfunction "A1_4") (pintype "passive"))
      (node (ref "R18") (pin "1") (pinfunction "1_1") (pintype "passive"))
      (node (ref "T8") (pin "G") (pinfunction "G_G") (pintype "passive"))
    )
    (net (code "46") (name "Net-(OC8-A2)") (class "Default")
      (node (ref "OC8") (pin "6") (pinfunction "A2_6") (pintype "passive"))
      (node (ref "R16") (pin "1") (pinfunction "1_1") (pintype "passive"))
    )
    (net (code "47") (name "Net-(OC8-C)") (class "Default")
      (node (ref "OC8") (pin "2") (pinfunction "C_2") (pintype "passive"))
      (node (ref "R64") (pin "2") (pinfunction "2_2") (pintype "passive"))
    )
    (net (code "48") (name "Net-(R2-Pad2)") (class "Default")
      (node (ref "R2") (pin "2") (pinfunction "2_2") (pintype "passive"))
      (node (ref "R45") (pin "1") (pinfunction "1_1") (pintype "passive"))
    )
    (net (code "49") (name "Net-(R10-Pad2)") (class "Default")
      (node (ref "R10") (pin "2") (pinfunction "2_2") (pintype "passive"))
      (node (ref "R11") (pin "1") (pinfunction "1_1") (pintype "passive"))
    )
    (net (code "50") (name "Net-(R11-Pad2)") (class "Default")
      (node (ref "R11") (pin "2") (pinfunction "2_2") (pintype "passive"))
      (node (ref "R54") (pin "2") (pinfunction "2_2") (pintype "passive"))
    )
    (net (code "51") (name "Net-(R12-Pad1)") (class "Default")
      (node (ref "R12") (pin "1") (pinfunction "1_1") (pintype "passive"))
      (node (ref "R9") (pin "2") (pinfunction "2_2") (pintype "passive"))
    )
    (net (code "52") (name "Net-(R12-Pad2)") (class "Default")
      (node (ref "R12") (pin "2") (pinfunction "2_2") (pintype "passive"))
      (node (ref "R21") (pin "1") (pinfunction "1_1") (pintype "passive"))
    )
    (net (code "53") (name "Net-(R13-Pad2)") (class "Default")
      (node (ref "R13") (pin "2") (pinfunction "2_2") (pintype "passive"))
      (node (ref "R49") (pin "1") (pinfunction "1_1") (pintype "passive"))
    )
    (net (code "54") (name "Net-(R14-Pad1)") (class "Default")
      (node (ref "R14") (pin "1") (pinfunction "1_1") (pintype "passive"))
      (node (ref "R33") (pin "2") (pinfunction "2_2") (pintype "passive"))
    )
    (net (code "55") (name "Net-(R14-Pad2)") (class "Default")
      (node (ref "R14") (pin "2") (pinfunction "2_2") (pintype "passive"))
      (node (ref "R34") (pin "1") (pinfunction "1_1") (pintype "passive"))
    )
    (net (code "56") (name "Net-(R15-Pad1)") (class "Default")
      (node (ref "R15") (pin "1") (pinfunction "1_1") (pintype "passive"))
      (node (ref "R28") (pin "2") (pinfunction "2_2") (pintype "passive"))
    )
    (net (code "57") (name "Net-(R16-Pad2)") (class "Default")
      (node (ref "R16") (pin "2") (pinfunction "2_2") (pintype "passive"))
      (node (ref "R29") (pin "1") (pinfunction "1_1") (pintype "passive"))
    )
    (net (code "58") (name "Net-(R22-Pad2)") (class "Default")
      (node (ref "R22") (pin "2") (pinfunction "2_2") (pintype "passive"))
      (node (ref "R51") (pin "1") (pinfunction "1_1") (pintype "passive"))
    )
    (net (code "59") (name "Net-(R23-Pad2)") (class "Default")
      (node (ref "R23") (pin "2") (pinfunction "2_2") (pintype "passive"))
      (node (ref "R25") (pin "1") (pinfunction "1_1") (pintype "passive"))
    )
    (net (code "60") (name "Net-(R24-Pad1)") (class "Default")
      (node (ref "R24") (pin "1") (pinfunction "1_1") (pintype "passive"))
      (node (ref "R31") (pin "2") (pinfunction "2_2") (pintype "passive"))
    )
    (net (code "61") (name "Net-(R24-Pad2)") (class "Default")
      (node (ref "R24") (pin "2") (pinfunction "2_2") (pintype "passive"))
      (node (ref "R32") (pin "1") (pinfunction "1_1") (pintype "passive"))
    )
    (net (code "62") (name "Net-(R25-Pad2)") (class "Default")
      (node (ref "R25") (pin "2") (pinfunction "2_2") (pintype "passive"))
      (node (ref "R26") (pin "2") (pinfunction "2_2") (pintype "passive"))
    )
    (net (code "63") (name "Net-(R27-Pad2)") (class "Default")
      (node (ref "R27") (pin "2") (pinfunction "2_2") (pintype "passive"))
      (node (ref "R28") (pin "1") (pinfunction "1_1") (pintype "passive"))
    )
    (net (code "64") (name "Net-(R29-Pad2)") (class "Default")
      (node (ref "R29") (pin "2") (pinfunction "2_2") (pintype "passive"))
      (node (ref "R30") (pin "1") (pinfunction "1_1") (pintype "passive"))
    )
    (net (code "65") (name "Net-(R35-Pad1)") (class "Default")
      (node (ref "R35") (pin "1") (pinfunction "1_1") (pintype "passive"))
      (node (ref "R4") (pin "2") (pinfunction "2_2") (pintype "passive"))
    )
    (net (code "66") (name "Net-(R35-Pad2)") (class "Default")
      (node (ref "R35") (pin "2") (pinfunction "2_2") (pintype "passive"))
      (node (ref "R36") (pin "1") (pinfunction "1_1") (pintype "passive"))
    )
    (net (code "67") (name "Net-(R37-Pad1)") (class "Default")
      (node (ref "R37") (pin "1") (pinfunction "1_1") (pintype "passive"))
      (node (ref "R8") (pin "2") (pinfunction "2_2") (pintype "passive"))
    )
    (net (code "68") (name "Net-(R37-Pad2)") (class "Default")
      (node (ref "R37") (pin "2") (pinfunction "2_2") (pintype "passive"))
      (node (ref "R38") (pin "1") (pinfunction "1_1") (pintype "passive"))
    )
    (net (code "69") (name "Net-(R39-Pad2)") (class "Default")
      (node (ref "R39") (pin "2") (pinfunction "2_2") (pintype "passive"))
      (node (ref "R40") (pin "1") (pinfunction "1_1") (pintype "passive"))
    )
    (net (code "70") (name "Net-(R40-Pad2)") (class "Default")
      (node (ref "R40") (pin "2") (pinfunction "2_2") (pintype "passive"))
      (node (ref "R41") (pin "1") (pinfunction "1_1") (pintype "passive"))
    )
    (net (code "71") (name "Net-(R42-Pad2)") (class "Default")
      (node (ref "R42") (pin "2") (pinfunction "2_2") (pintype "passive"))
      (node (ref "R43") (pin "1") (pinfunction "1_1") (pintype "passive"))
    )
    (net (code "72") (name "Net-(R43-Pad2)") (class "Default")
      (node (ref "R43") (pin "2") (pinfunction "2_2") (pintype "passive"))
      (node (ref "R44") (pin "1") (pinfunction "1_1") (pintype "passive"))
    )
    (net (code "73") (name "Net-(R45-Pad2)") (class "Default")
      (node (ref "R45") (pin "2") (pinfunction "2_2") (pintype "passive"))
      (node (ref "R46") (pin "1") (pinfunction "1_1") (pintype "passive"))
    )
    (net (code "74") (name "Net-(R47-Pad1)") (class "Default")
      (node (ref "R47") (pin "1") (pinfunction "1_1") (pintype "passive"))
      (node (ref "R6") (pin "2") (pinfunction "2_2") (pintype "passive"))
    )
    (net (code "75") (name "Net-(R47-Pad2)") (class "Default")
      (node (ref "R47") (pin "2") (pinfunction "2_2") (pintype "passive"))
      (node (ref "R48") (pin "1") (pinfunction "1_1") (pintype "passive"))
    )
    (net (code "76") (name "Net-(R49-Pad2)") (class "Default")
      (node (ref "R49") (pin "2") (pinfunction "2_2") (pintype "passive"))
      (node (ref "R50") (pin "1") (pinfunction "1_1") (pintype "passive"))
    )
    (net (code "77") (name "Net-(R51-Pad2)") (class "Default")
      (node (ref "R51") (pin "2") (pinfunction "2_2") (pintype "passive"))
      (node (ref "R55") (pin "2") (pinfunction "2_2") (pintype "passive"))
    )
    (net (code "78") (name "Net-(R52-Pad2)") (class "Default")
      (node (ref "R52") (pin "2") (pinfunction "2_2") (pintype "passive"))
      (node (ref "R53") (pin "1") (pinfunction "1_1") (pintype "passive"))
    )
    (net (code "79") (name "Net-(R53-Pad2)") (class "Default")
      (node (ref "R53") (pin "2") (pinfunction "2_2") (pintype "passive"))
      (node (ref "R56") (pin "2") (pinfunction "2_2") (pintype "passive"))
    )
    (net (code "80") (name "OUT1") (class "Default")
      (node (ref "JP1") (pin "3") (pinfunction "3_3") (pintype "passive"))
      (node (ref "R63") (pin "1") (pinfunction "1_1") (pintype "passive"))
    )
    (net (code "81") (name "OUT2") (class "Default")
      (node (ref "JP1") (pin "5") (pinfunction "5_5") (pintype "passive"))
      (node (ref "R67") (pin "1") (pinfunction "1_1") (pintype "passive"))
    )
    (net (code "82") (name "OUT3") (class "Default")
      (node (ref "JP1") (pin "7") (pinfunction "7_7") (pintype "passive"))
      (node (ref "R62") (pin "1") (pinfunction "1_1") (pintype "passive"))
    )
    (net (code "83") (name "OUT4") (class "Default")
      (node (ref "JP1") (pin "9") (pinfunction "9_9") (pintype "passive"))
      (node (ref "R66") (pin "1") (pinfunction "1_1") (pintype "passive"))
    )
    (net (code "84") (name "OUT5") (class "Default")
      (node (ref "JP1") (pin "4") (pinfunction "4_4") (pintype "passive"))
      (node (ref "R60") (pin "1") (pinfunction "1_1") (pintype "passive"))
    )
    (net (code "85") (name "OUT6") (class "Default")
      (node (ref "JP1") (pin "6") (pinfunction "6_6") (pintype "passive"))
      (node (ref "R65") (pin "1") (pinfunction "1_1") (pintype "passive"))
    )
    (net (code "86") (name "OUT7") (class "Default")
      (node (ref "JP1") (pin "8") (pinfunction "8_8") (pintype "passive"))
      (node (ref "R61") (pin "1") (pinfunction "1_1") (pintype "passive"))
    )
    (net (code "87") (name "OUT8") (class "Default")
      (node (ref "JP1") (pin "10") (pinfunction "10_10") (pintype "passive"))
      (node (ref "R64") (pin "1") (pinfunction "1_1") (pintype "passive"))
    )
    (net (code "88") (name "unconnected-(U$14-PadTOA)") (class "Default")
      (node (ref "U$14") (pin "TOA") (pinfunction "TOA_TOA") (pintype "bidirectional"))
    )
    (net (code "89") (name "unconnected-(U$14-PadTOB)") (class "Default")
      (node (ref "U$14") (pin "TOB") (pinfunction "TOB_TOB") (pintype "bidirectional"))
    )
    (net (code "90") (name "unconnected-(U$15-PadTOA)") (class "Default")
      (node (ref "U$15") (pin "TOA") (pinfunction "TOA_TOA") (pintype "bidirectional"))
    )
    (net (code "91") (name "unconnected-(U$15-PadTOB)") (class "Default")
      (node (ref "U$15") (pin "TOB") (pinfunction "TOB_TOB") (pintype "bidirectional"))
    )
    (net (code "92") (name "unconnected-(U$16-PadTOA)") (class "Default")
      (node (ref "U$16") (pin "TOA") (pinfunction "TOA_TOA") (pintype "bidirectional"))
    )
    (net (code "93") (name "unconnected-(U$16-PadTOB)") (class "Default")
      (node (ref "U$16") (pin "TOB") (pinfunction "TOB_TOB") (pintype "bidirectional"))
    )
    (net (code "94") (name "unconnected-(U$17-PadTOA)") (class "Default")
      (node (ref "U$17") (pin "TOA") (pinfunction "TOA_TOA") (pintype "bidirectional"))
    )
    (net (code "95") (name "unconnected-(U$17-PadTOB)") (class "Default")
      (node (ref "U$17") (pin "TOB") (pinfunction "TOB_TOB") (pintype "bidirectional"))
    )
    (net (code "96") (name "unconnected-(U$18-PadTOA)") (class "Default")
      (node (ref "U$18") (pin "TOA") (pinfunction "TOA_TOA") (pintype "bidirectional"))
    )
    (net (code "97") (name "unconnected-(U$18-PadTOB)") (class "Default")
      (node (ref "U$18") (pin "TOB") (pinfunction "TOB_TOB") (pintype "bidirectional"))
    )
    (net (code "98") (name "unconnected-(U$19-PadTOA)") (class "Default")
      (node (ref "U$19") (pin "TOA") (pinfunction "TOA_TOA") (pintype "bidirectional"))
    )
    (net (code "99") (name "unconnected-(U$19-PadTOB)") (class "Default")
      (node (ref "U$19") (pin "TOB") (pinfunction "TOB_TOB") (pintype "bidirectional"))
    )
    (net (code "100") (name "unconnected-(U$20-PadTOA)") (class "Default")
      (node (ref "U$20") (pin "TOA") (pinfunction "TOA_TOA") (pintype "bidirectional"))
    )
    (net (code "101") (name "unconnected-(U$20-PadTOB)") (class "Default")
      (node (ref "U$20") (pin "TOB") (pinfunction "TOB_TOB") (pintype "bidirectional"))
    )
    (net (code "102") (name "unconnected-(U$21-PadTOA)") (class "Default")
      (node (ref "U$21") (pin "TOA") (pinfunction "TOA_TOA") (pintype "bidirectional"))
    )
    (net (code "103") (name "unconnected-(U$21-PadTOB)") (class "Default")
      (node (ref "U$21") (pin "TOB") (pinfunction "TOB_TOB") (pintype "bidirectional"))
    )
    (net (code "104") (name "unconnected-(U$22-PadTOA)") (class "Default")
      (node (ref "U$22") (pin "TOA") (pinfunction "TOA_TOA") (pintype "bidirectional"))
    )
    (net (code "105") (name "unconnected-(U$22-PadTOB)") (class "Default")
      (node (ref "U$22") (pin "TOB") (pinfunction "TOB_TOB") (pintype "bidirectional"))
    )
    (net (code "106") (name "unconnected-(U$23-PadTOA)") (class "Default")
      (node (ref "U$23") (pin "TOA") (pinfunction "TOA_TOA") (pintype "bidirectional"))
    )
    (net (code "107") (name "unconnected-(U$23-PadTOB)") (class "Default")
      (node (ref "U$23") (pin "TOB") (pinfunction "TOB_TOB") (pintype "bidirectional"))
    )
    (net (code "108") (name "unconnected-(U$24-PadTOA)") (class "Default")
      (node (ref "U$24") (pin "TOA") (pinfunction "TOA_TOA") (pintype "bidirectional"))
    )
    (net (code "109") (name "unconnected-(U$24-PadTOB)") (class "Default")
      (node (ref "U$24") (pin "TOB") (pinfunction "TOB_TOB") (pintype "bidirectional"))
    )
    (net (code "110") (name "unconnected-(U$25-PadTOA)") (class "Default")
      (node (ref "U$25") (pin "TOA") (pinfunction "TOA_TOA") (pintype "bidirectional"))
    )
    (net (code "111") (name "unconnected-(U$25-PadTOB)") (class "Default")
      (node (ref "U$25") (pin "TOB") (pinfunction "TOB_TOB") (pintype "bidirectional"))
    )
    (net (code "112") (name "unconnected-(U$26-PadTOA)") (class "Default")
      (node (ref "U$26") (pin "TOA") (pinfunction "TOA_TOA") (pintype "bidirectional"))
    )
    (net (code "113") (name "unconnected-(U$26-PadTOB)") (class "Default")
      (node (ref "U$26") (pin "TOB") (pinfunction "TOB_TOB") (pintype "bidirectional"))
    )
    (net (code "114") (name "unconnected-(U$27-PadTOA)") (class "Default")
      (node (ref "U$27") (pin "TOA") (pinfunction "TOA_TOA") (pintype "bidirectional"))
    )
    (net (code "115") (name "unconnected-(U$27-PadTOB)") (class "Default")
      (node (ref "U$27") (pin "TOB") (pinfunction "TOB_TOB") (pintype "bidirectional"))
    )
    (net (code "116") (name "unconnected-(U$28-PadTOA)") (class "Default")
      (node (ref "U$28") (pin "TOA") (pinfunction "TOA_TOA") (pintype "bidirectional"))
    )
    (net (code "117") (name "unconnected-(U$28-PadTOB)") (class "Default")
      (node (ref "U$28") (pin "TOB") (pinfunction "TOB_TOB") (pintype "bidirectional"))
    )
    (net (code "118") (name "unconnected-(U$29-PadTOA)") (class "Default")
      (node (ref "U$29") (pin "TOA") (pinfunction "TOA_TOA") (pintype "bidirectional"))
    )
    (net (code "119") (name "unconnected-(U$29-PadTOB)") (class "Default")
      (node (ref "U$29") (pin "TOB") (pinfunction "TOB_TOB") (pintype "bidirectional"))
    )
  )
)
